# RelayDriver.net
KiCad netlist of a schematic drawn in Altium Designer
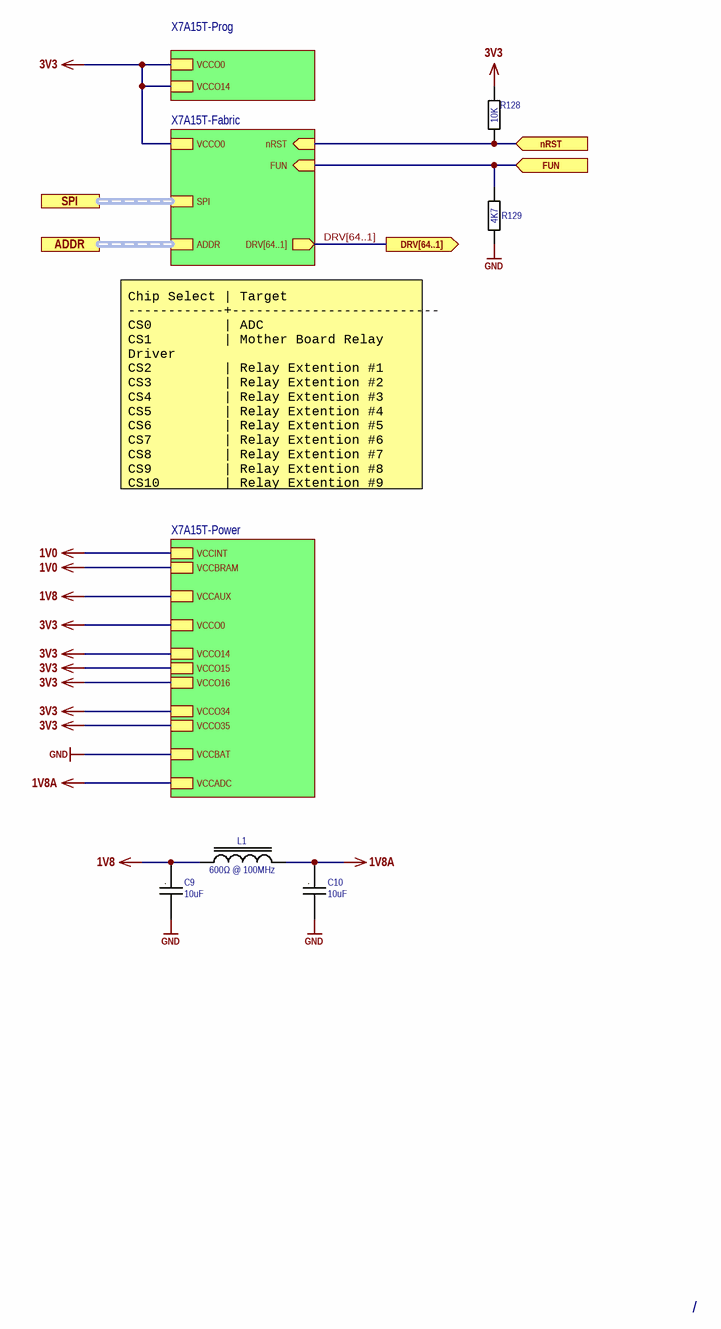
[diagram p0: RelayDriver.SchDoc]

(export (version "E")
  (design (tool "Eeschema 10.0.6"))
  (components
    (comp (ref "C9")
      (value "10uF")
      (footprint "C0805 Reflow")
      (description "CAP CER 10UF 10V X7R 0805")
      (fields
        (field (name "TOLERANCE") "±10%")
        (field (name "02. DISTRIBUTOR PART NUMBER") "1276-1764-6-ND")
        (field (name "13. CREATED DATE/NAME") "AUG2018/Hören")
      )
      (libsource (lib "chickenfood") (part "C"))
    )
    (comp (ref "C10")
      (value "10uF")
      (footprint "C0805 Reflow")
      (description "CAP CER 10UF 10V X7R 0805")
      (fields
        (field (name "TOLERANCE") "±10%")
        (field (name "02. DISTRIBUTOR PART NUMBER") "1276-1764-6-ND")
        (field (name "13. CREATED DATE/NAME") "AUG2018/Hören")
      )
      (libsource (lib "chickenfood") (part "C"))
    )
    (comp (ref "L1")
      (value "L")
      (footprint "FB0805")
      (description "FERRITE BEAD 600 OHM 0805 1LN")
      (fields
        (field (name "NOMINAL IMPEDANCE") "600Ω @ 100MHz")
        (field (name "02. DISTRIBUTOR PART NUMBER") "732-1620-6-ND")
        (field (name "07. MANUFACTURER  PART NUMBER") "742792040")
        (field (name "13. CREATED DATE/NAME") "AUG2018/Hören")
      )
      (libsource (lib "chickenfood") (part "FB"))
    )
    (comp (ref "R128")
      (value "10K")
      (footprint "R0402 Reflow")
      (description "RES SMD 10K OHM 1% 1/16W 0402")
      (fields
        (field (name "TOLERANCE") "±1%")
        (field (name "02. DISTRIBUTOR PART NUMBER") "311-10.0KLRDKR-ND")
        (field (name "13. CREATED DATE/NAME") "AUG2018/Hören")
      )
      (libsource (lib "") (part "R_1"))
    )
    (comp (ref "R129")
      (value "4K7")
      (footprint "R0402 Reflow")
      (description "RES SMD 4.7K OHM 1% 1/16W 0402")
      (fields
        (field (name "TOLERANCE") "±1%")
        (field (name "02. DISTRIBUTOR PART NUMBER") "311-4.7KLRDKR-ND")
        (field (name "13. CREATED DATE/NAME") "AUG2018/Hören")
      )
      (libsource (lib "chickenfood") (part "R"))
    )
  )
  (nets
    (net (code "69") (name "/FUN") (class "Default")
      (node (ref "R129") (pin "2") (pinfunction "2_2") (pintype "passive"))
    )
    (net (code "71") (name "/nRST") (class "Default")
      (node (ref "R128") (pin "2") (pinfunction "2_2") (pintype "passive"))
    )
    (net (code "73") (name "1V8") (class "Default")
      (node (ref "C9") (pin "1") (pinfunction "1_1") (pintype "passive"))
      (node (ref "L1") (pin "1") (pinfunction "1_1") (pintype "passive"))
    )
    (net (code "74") (name "1V8A") (class "Default")
      (node (ref "C10") (pin "1") (pinfunction "1_1") (pintype "passive"))
      (node (ref "L1") (pin "2") (pinfunction "2_2") (pintype "passive"))
    )
    (net (code "75") (name "3V3") (class "Default")
      (node (ref "R128") (pin "1") (pinfunction "1_1") (pintype "passive"))
    )
    (net (code "76") (name "GND") (class "Default")
      (node (ref "C10") (pin "2") (pinfunction "2_2") (pintype "passive"))
      (node (ref "C9") (pin "2") (pinfunction "2_2") (pintype "passive"))
      (node (ref "R129") (pin "1") (pinfunction "1_1") (pintype "passive"))
    )
  )
)
